# 07-ZYNQ_BANK_502.net
KiCad netlist of a schematic drawn in Altium Designer
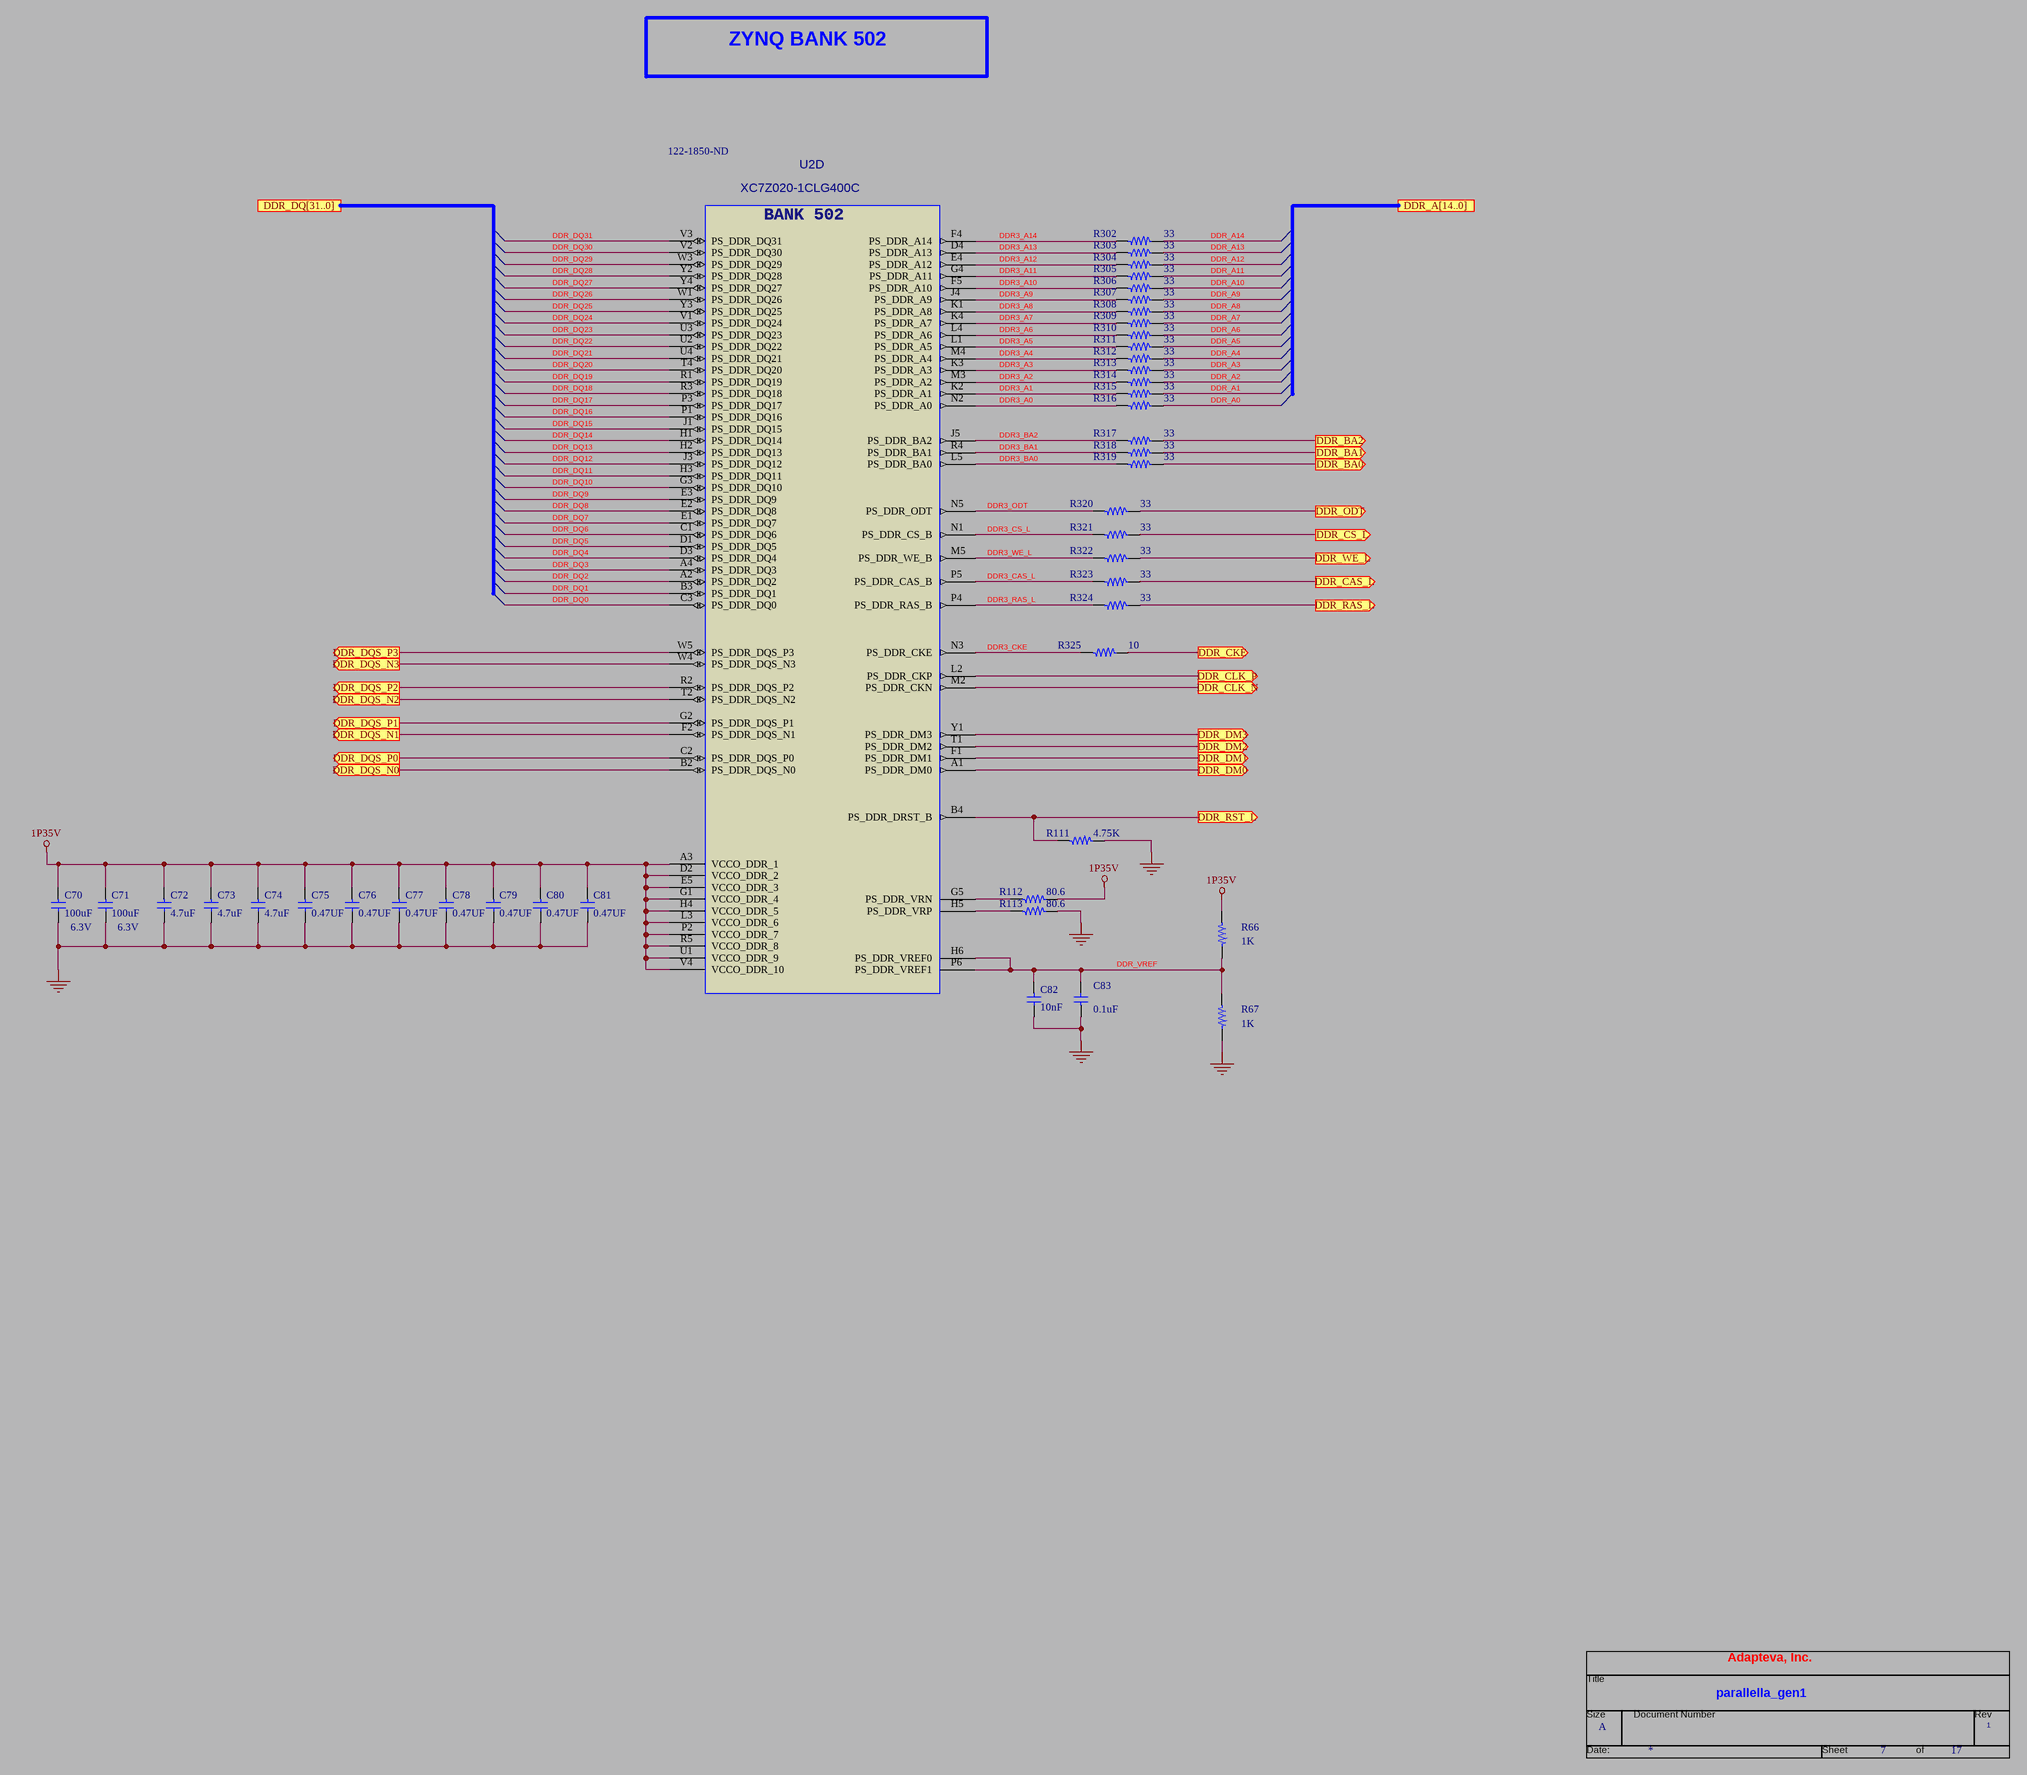
[diagram p0: 07-ZYNQ BANK 502.SchDoc]

(export (version "E")
  (design (tool "Eeschema 10.0.6"))
  (components
    (comp (ref "C70")
      (value "100uF")
      (footprint "C1210")
      (description "CAP, 1210, 100UF, X5R, 6.3V, LOW ESR")
      (fields
        (field (name "VOLTAGE") "6.3V")
        (field (name "MFG PART NO") "GRM32ER60J107ME20L")
        (field (name "MFG") "MURATA")
      )
      (libsource (lib "*") (part "CAP1210_100UF_X5R_LOESR"))
    )
    (comp (ref "C71")
      (value "100uF")
      (footprint "C1210")
      (description "CAP, 1210, 100UF, X5R, 6.3V, LOW ESR")
      (fields
        (field (name "VOLTAGE") "6.3V")
        (field (name "MFG PART NO") "GRM32ER60J107ME20L")
        (field (name "MFG") "MURATA")
      )
      (libsource (lib "*") (part "CAP1210_100UF_X5R_LOESR"))
    )
    (comp (ref "C72")
      (value "4.7uF")
      (footprint "C0402")
      (description "CAP, 0402, 4.7UF, X5R, 6.3V")
      (fields (field (name "MFG PART NO") "C1005X5R0J475K") (field (name "MFG") "TDK"))
      (libsource (lib "*") (part "CAP0402_4P7UF_X5R"))
    )
    (comp (ref "C73")
      (value "4.7uF")
      (footprint "C0402")
      (description "CAP, 0402, 4.7UF, X5R, 6.3V")
      (fields (field (name "MFG PART NO") "C1005X5R0J475K") (field (name "MFG") "TDK"))
      (libsource (lib "*") (part "CAP0402_4P7UF_X5R"))
    )
    (comp (ref "C74")
      (value "4.7uF")
      (footprint "C0402")
      (description "CAP, 0402, 4.7UF, X5R, 6.3V")
      (fields (field (name "MFG PART NO") "C1005X5R0J475K") (field (name "MFG") "TDK"))
      (libsource (lib "*") (part "CAP0402_4P7UF_X5R"))
    )
    (comp (ref "C75")
      (value "0.47UF")
      (footprint "C0402")
      (description "CAP, 0402, 0.47UF, X5R, 16V")
      (fields (field (name "MFG") "TDK") (field (name "MFG PART NO") "C1005X5R1C474K"))
      (libsource (lib "*") (part "CAP0402_0P47UF_X5R"))
    )
    (comp (ref "C76")
      (value "0.47UF")
      (footprint "C0402")
      (description "CAP, 0402, 0.47UF, X5R, 16V")
      (fields (field (name "MFG") "TDK") (field (name "MFG PART NO") "C1005X5R1C474K"))
      (libsource (lib "*") (part "CAP0402_0P47UF_X5R"))
    )
    (comp (ref "C77")
      (value "0.47UF")
      (footprint "C0402")
      (description "CAP, 0402, 0.47UF, X5R, 16V")
      (fields (field (name "MFG") "TDK") (field (name "MFG PART NO") "C1005X5R1C474K"))
      (libsource (lib "*") (part "CAP0402_0P47UF_X5R"))
    )
    (comp (ref "C78")
      (value "0.47UF")
      (footprint "C0402")
      (description "CAP, 0402, 0.47UF, X5R, 16V")
      (fields (field (name "MFG") "TDK") (field (name "MFG PART NO") "C1005X5R1C474K"))
      (libsource (lib "*") (part "CAP0402_0P47UF_X5R"))
    )
    (comp (ref "C79")
      (value "0.47UF")
      (footprint "C0402")
      (description "CAP, 0402, 0.47UF, X5R, 16V")
      (fields (field (name "MFG") "TDK") (field (name "MFG PART NO") "C1005X5R1C474K"))
      (libsource (lib "*") (part "CAP0402_0P47UF_X5R"))
    )
    (comp (ref "C80")
      (value "0.47UF")
      (footprint "C0402")
      (description "CAP, 0402, 0.47UF, X5R, 16V")
      (fields (field (name "MFG") "TDK") (field (name "MFG PART NO") "C1005X5R1C474K"))
      (libsource (lib "*") (part "CAP0402_0P47UF_X5R"))
    )
    (comp (ref "C81")
      (value "0.47UF")
      (footprint "C0402")
      (description "CAP, 0402, 0.47UF, X5R, 16V")
      (fields (field (name "MFG") "TDK") (field (name "MFG PART NO") "C1005X5R1C474K"))
      (libsource (lib "*") (part "CAP0402_0P47UF_X5R"))
    )
    (comp (ref "C82")
      (value "10nF")
      (footprint "C0402")
      (description "CAP, 0402, 10NF, X7R, 16V")
      (fields (field (name "MFG") "TDK") (field (name "MFG PART NO") "C1005X7R1C103K"))
      (libsource (lib "*") (part "CAP0402_10NF_X7R_16V"))
    )
    (comp (ref "C83")
      (value "0.1uF")
      (footprint "C0402")
      (description "CAP, 0402, 0.1UF, X5R, 35V")
      (fields (field (name "MFG PART NO") "GMK105BJ104KV-F") (field (name "MFG") "TAIYO YUDEN"))
      (libsource (lib "*") (part "CAP0402_0P1UF_X5R_35V"))
    )
    (comp (ref "R66")
      (value "1K")
      (footprint "R0402")
      (description "RES, 0402, 1K")
      (fields (field (name "MFG") "VISHAY") (field (name "MFG PART NO") "CRCW04021K00FKED"))
      (libsource (lib "*") (part "RES0402_1K"))
    )
    (comp (ref "R67")
      (value "1K")
      (footprint "R0402")
      (description "RES, 0402, 1K")
      (fields (field (name "MFG") "VISHAY") (field (name "MFG PART NO") "CRCW04021K00FKED"))
      (libsource (lib "*") (part "RES0402_1K"))
    )
    (comp (ref "R111")
      (value "4.75K")
      (footprint "R0402")
      (description "RES, 0402, 4.75K, 1%")
      (fields (field (name "MFG") "VISHAY") (field (name "MFG PART NO") "CRCW04024K75FKED"))
      (libsource (lib "*") (part "RES0402_4K75"))
    )
    (comp (ref "R112")
      (value "80.6")
      (footprint "R0402")
      (description "RES, 0402, 80.6, 1%")
      (fields (field (name "MFG") "VISHAY") (field (name "MFG PART NO") "CRCW040280R6FKED"))
      (libsource (lib "*") (part "RES0402_80P6"))
    )
    (comp (ref "R113")
      (value "80.6")
      (footprint "R0402")
      (description "RES, 0402, 80.6, 1%")
      (fields (field (name "MFG") "VISHAY") (field (name "MFG PART NO") "CRCW040280R6FKED"))
      (libsource (lib "*") (part "RES0402_80P6"))
    )
    (comp (ref "R302")
      (value "33")
      (footprint "R0402")
      (description "RES, 0402, 33, 1%")
      (fields (field (name "MFG") "VISHAY") (field (name "MFG PART NO") "CRCW040233R0FKED"))
      (libsource (lib "*") (part "RES0402_33"))
    )
    (comp (ref "R303")
      (value "33")
      (footprint "R0402")
      (description "RES, 0402, 33, 1%")
      (fields (field (name "MFG") "VISHAY") (field (name "MFG PART NO") "CRCW040233R0FKED"))
      (libsource (lib "*") (part "RES0402_33"))
    )
    (comp (ref "R304")
      (value "33")
      (footprint "R0402")
      (description "RES, 0402, 33, 1%")
      (fields (field (name "MFG") "VISHAY") (field (name "MFG PART NO") "CRCW040233R0FKED"))
      (libsource (lib "*") (part "RES0402_33"))
    )
    (comp (ref "R305")
      (value "33")
      (footprint "R0402")
      (description "RES, 0402, 33, 1%")
      (fields (field (name "MFG") "VISHAY") (field (name "MFG PART NO") "CRCW040233R0FKED"))
      (libsource (lib "*") (part "RES0402_33"))
    )
    (comp (ref "R306")
      (value "33")
      (footprint "R0402")
      (description "RES, 0402, 33, 1%")
      (fields (field (name "MFG") "VISHAY") (field (name "MFG PART NO") "CRCW040233R0FKED"))
      (libsource (lib "*") (part "RES0402_33"))
    )
    (comp (ref "R307")
      (value "33")
      (footprint "R0402")
      (description "RES, 0402, 33, 1%")
      (fields (field (name "MFG") "VISHAY") (field (name "MFG PART NO") "CRCW040233R0FKED"))
      (libsource (lib "*") (part "RES0402_33"))
    )
    (comp (ref "R308")
      (value "33")
      (footprint "R0402")
      (description "RES, 0402, 33, 1%")
      (fields (field (name "MFG") "VISHAY") (field (name "MFG PART NO") "CRCW040233R0FKED"))
      (libsource (lib "*") (part "RES0402_33"))
    )
    (comp (ref "R309")
      (value "33")
      (footprint "R0402")
      (description "RES, 0402, 33, 1%")
      (fields (field (name "MFG") "VISHAY") (field (name "MFG PART NO") "CRCW040233R0FKED"))
      (libsource (lib "*") (part "RES0402_33"))
    )
    (comp (ref "R310")
      (value "33")
      (footprint "R0402")
      (description "RES, 0402, 33, 1%")
      (fields (field (name "MFG") "VISHAY") (field (name "MFG PART NO") "CRCW040233R0FKED"))
      (libsource (lib "*") (part "RES0402_33"))
    )
    (comp (ref "R311")
      (value "33")
      (footprint "R0402")
      (description "RES, 0402, 33, 1%")
      (fields (field (name "MFG") "VISHAY") (field (name "MFG PART NO") "CRCW040233R0FKED"))
      (libsource (lib "*") (part "RES0402_33"))
    )
    (comp (ref "R312")
      (value "33")
      (footprint "R0402")
      (description "RES, 0402, 33, 1%")
      (fields (field (name "MFG") "VISHAY") (field (name "MFG PART NO") "CRCW040233R0FKED"))
      (libsource (lib "*") (part "RES0402_33"))
    )
    (comp (ref "R313")
      (value "33")
      (footprint "R0402")
      (description "RES, 0402, 33, 1%")
      (fields (field (name "MFG") "VISHAY") (field (name "MFG PART NO") "CRCW040233R0FKED"))
      (libsource (lib "*") (part "RES0402_33"))
    )
    (comp (ref "R314")
      (value "33")
      (footprint "R0402")
      (description "RES, 0402, 33, 1%")
      (fields (field (name "MFG") "VISHAY") (field (name "MFG PART NO") "CRCW040233R0FKED"))
      (libsource (lib "*") (part "RES0402_33"))
    )
    (comp (ref "R315")
      (value "33")
      (footprint "R0402")
      (description "RES, 0402, 33, 1%")
      (fields (field (name "MFG") "VISHAY") (field (name "MFG PART NO") "CRCW040233R0FKED"))
      (libsource (lib "*") (part "RES0402_33"))
    )
    (comp (ref "R316")
      (value "33")
      (footprint "R0402")
      (description "RES, 0402, 33, 1%")
      (fields (field (name "MFG") "VISHAY") (field (name "MFG PART NO") "CRCW040233R0FKED"))
      (libsource (lib "*") (part "RES0402_33"))
    )
    (comp (ref "R317")
      (value "33")
      (footprint "R0402")
      (description "RES, 0402, 33, 1%")
      (fields (field (name "MFG") "VISHAY") (field (name "MFG PART NO") "CRCW040233R0FKED"))
      (libsource (lib "*") (part "RES0402_33"))
    )
    (comp (ref "R318")
      (value "33")
      (footprint "R0402")
      (description "RES, 0402, 33, 1%")
      (fields (field (name "MFG") "VISHAY") (field (name "MFG PART NO") "CRCW040233R0FKED"))
      (libsource (lib "*") (part "RES0402_33"))
    )
    (comp (ref "R319")
      (value "33")
      (footprint "R0402")
      (description "RES, 0402, 33, 1%")
      (fields (field (name "MFG") "VISHAY") (field (name "MFG PART NO") "CRCW040233R0FKED"))
      (libsource (lib "*") (part "RES0402_33"))
    )
    (comp (ref "R320")
      (value "33")
      (footprint "R0402")
      (description "RES, 0402, 33, 1%")
      (fields (field (name "MFG") "VISHAY") (field (name "MFG PART NO") "CRCW040233R0FKED"))
      (libsource (lib "*") (part "RES0402_33"))
    )
    (comp (ref "R321")
      (value "33")
      (footprint "R0402")
      (description "RES, 0402, 33, 1%")
      (fields (field (name "MFG") "VISHAY") (field (name "MFG PART NO") "CRCW040233R0FKED"))
      (libsource (lib "*") (part "RES0402_33"))
    )
    (comp (ref "R322")
      (value "33")
      (footprint "R0402")
      (description "RES, 0402, 33, 1%")
      (fields (field (name "MFG") "VISHAY") (field (name "MFG PART NO") "CRCW040233R0FKED"))
      (libsource (lib "*") (part "RES0402_33"))
    )
    (comp (ref "R323")
      (value "33")
      (footprint "R0402")
      (description "RES, 0402, 33, 1%")
      (fields (field (name "MFG") "VISHAY") (field (name "MFG PART NO") "CRCW040233R0FKED"))
      (libsource (lib "*") (part "RES0402_33"))
    )
    (comp (ref "R324")
      (value "33")
      (footprint "R0402")
      (description "RES, 0402, 33, 1%")
      (fields (field (name "MFG") "VISHAY") (field (name "MFG PART NO") "CRCW040233R0FKED"))
      (libsource (lib "*") (part "RES0402_33"))
    )
    (comp (ref "R325")
      (value "10")
      (footprint "R0402")
      (description "RES, 0402, 10, 1%")
      (fields (field (name "MFG PART NO") "CRCW040210R0FKED") (field (name "MFG") "VISHAY"))
      (libsource (lib "*") (part "RES0402_10"))
    )
    (comp (ref "U2")
      (value "7Z020-CLG400")
      (footprint "CBGA400_17SQ_1P6H_P8MMP")
      (description "IC, EPP, XILINX, ZYNQ, 7Z020, CLG400")
      (fields
        (field (name "VENDOR PN") "XC7Z020-1CLG400C")
        (field (name "SUPPLIER PART NUMBER 1") "122-1850-ND")
      )
      (libsource (lib "*") (part "ZYNQ_7Z020_CLG400"))
    )
  )
  (nets
    (net (code "1") (name "/DDR3_A0") (class "Default")
      (node (ref "R316") (pin "1") (pinfunction "1_1") (pintype "passive"))
      (node (ref "U2") (pin "N2") (pinfunction "PS_DDR_A0_N2") (pintype "output"))
    )
    (net (code "2") (name "/DDR3_A1") (class "Default")
      (node (ref "R315") (pin "1") (pinfunction "1_1") (pintype "passive"))
      (node (ref "U2") (pin "K2") (pinfunction "PS_DDR_A1_K2") (pintype "output"))
    )
    (net (code "3") (name "/DDR3_A2") (class "Default")
      (node (ref "R314") (pin "1") (pinfunction "1_1") (pintype "passive"))
      (node (ref "U2") (pin "M3") (pinfunction "PS_DDR_A2_M3") (pintype "output"))
    )
    (net (code "4") (name "/DDR3_A3") (class "Default")
      (node (ref "R313") (pin "1") (pinfunction "1_1") (pintype "passive"))
      (node (ref "U2") (pin "K3") (pinfunction "PS_DDR_A3_K3") (pintype "output"))
    )
    (net (code "5") (name "/DDR3_A4") (class "Default")
      (node (ref "R312") (pin "1") (pinfunction "1_1") (pintype "passive"))
      (node (ref "U2") (pin "M4") (pinfunction "PS_DDR_A4_M4") (pintype "output"))
    )
    (net (code "6") (name "/DDR3_A5") (class "Default")
      (node (ref "R311") (pin "1") (pinfunction "1_1") (pintype "passive"))
      (node (ref "U2") (pin "L1") (pinfunction "PS_DDR_A5_L1") (pintype "output"))
    )
    (net (code "7") (name "/DDR3_A6") (class "Default")
      (node (ref "R310") (pin "1") (pinfunction "1_1") (pintype "passive"))
      (node (ref "U2") (pin "L4") (pinfunction "PS_DDR_A6_L4") (pintype "output"))
    )
    (net (code "8") (name "/DDR3_A7") (class "Default")
      (node (ref "R309") (pin "1") (pinfunction "1_1") (pintype "passive"))
      (node (ref "U2") (pin "K4") (pinfunction "PS_DDR_A7_K4") (pintype "output"))
    )
    (net (code "9") (name "/DDR3_A8") (class "Default")
      (node (ref "R308") (pin "1") (pinfunction "1_1") (pintype "passive"))
      (node (ref "U2") (pin "K1") (pinfunction "PS_DDR_A8_K1") (pintype "output"))
    )
    (net (code "10") (name "/DDR3_A9") (class "Default")
      (node (ref "R307") (pin "1") (pinfunction "1_1") (pintype "passive"))
      (node (ref "U2") (pin "J4") (pinfunction "PS_DDR_A9_J4") (pintype "output"))
    )
    (net (code "11") (name "/DDR3_A10") (class "Default")
      (node (ref "R306") (pin "1") (pinfunction "1_1") (pintype "passive"))
      (node (ref "U2") (pin "F5") (pinfunction "PS_DDR_A10_F5") (pintype "output"))
    )
    (net (code "12") (name "/DDR3_A11") (class "Default")
      (node (ref "R305") (pin "1") (pinfunction "1_1") (pintype "passive"))
      (node (ref "U2") (pin "G4") (pinfunction "PS_DDR_A11_G4") (pintype "output"))
    )
    (net (code "13") (name "/DDR3_A12") (class "Default")
      (node (ref "R304") (pin "1") (pinfunction "1_1") (pintype "passive"))
      (node (ref "U2") (pin "E4") (pinfunction "PS_DDR_A12_E4") (pintype "output"))
    )
    (net (code "14") (name "/DDR3_A13") (class "Default")
      (node (ref "R303") (pin "1") (pinfunction "1_1") (pintype "passive"))
      (node (ref "U2") (pin "D4") (pinfunction "PS_DDR_A13_D4") (pintype "output"))
    )
    (net (code "15") (name "/DDR3_A14") (class "Default")
      (node (ref "R302") (pin "1") (pinfunction "1_1") (pintype "passive"))
      (node (ref "U2") (pin "F4") (pinfunction "PS_DDR_A14_F4") (pintype "output"))
    )
    (net (code "16") (name "/DDR3_BA0") (class "Default")
      (node (ref "R319") (pin "1") (pinfunction "1_1") (pintype "passive"))
      (node (ref "U2") (pin "L5") (pinfunction "PS_DDR_BA0_L5") (pintype "output"))
    )
    (net (code "17") (name "/DDR3_BA1") (class "Default")
      (node (ref "R318") (pin "1") (pinfunction "1_1") (pintype "passive"))
      (node (ref "U2") (pin "R4") (pinfunction "PS_DDR_BA1_R4") (pintype "output"))
    )
    (net (code "18") (name "/DDR3_BA2") (class "Default")
      (node (ref "R317") (pin "1") (pinfunction "1_1") (pintype "passive"))
      (node (ref "U2") (pin "J5") (pinfunction "PS_DDR_BA2_J5") (pintype "output"))
    )
    (net (code "19") (name "/DDR3_CAS_L") (class "Default")
      (node (ref "R323") (pin "1") (pinfunction "1_1") (pintype "passive"))
      (node (ref "U2") (pin "P5") (pinfunction "PS_DDR_CAS_B_P5") (pintype "output"))
    )
    (net (code "20") (name "/DDR3_CKE") (class "Default")
      (node (ref "R325") (pin "1") (pinfunction "1_1") (pintype "passive"))
      (node (ref "U2") (pin "N3") (pinfunction "PS_DDR_CKE_N3") (pintype "output"))
    )
    (net (code "21") (name "/DDR3_CS_L") (class "Default")
      (node (ref "R321") (pin "1") (pinfunction "1_1") (pintype "passive"))
      (node (ref "U2") (pin "N1") (pinfunction "PS_DDR_CS_B_N1") (pintype "output"))
    )
    (net (code "22") (name "/DDR3_ODT") (class "Default")
      (node (ref "R320") (pin "1") (pinfunction "1_1") (pintype "passive"))
      (node (ref "U2") (pin "N5") (pinfunction "PS_DDR_ODT_N5") (pintype "output"))
    )
    (net (code "23") (name "/DDR3_RAS_L") (class "Default")
      (node (ref "R324") (pin "1") (pinfunction "1_1") (pintype "passive"))
      (node (ref "U2") (pin "P4") (pinfunction "PS_DDR_RAS_B_P4") (pintype "output"))
    )
    (net (code "24") (name "/DDR3_WE_L") (class "Default")
      (node (ref "R322") (pin "1") (pinfunction "1_1") (pintype "passive"))
      (node (ref "U2") (pin "M5") (pinfunction "PS_DDR_WE_B_M5") (pintype "output"))
    )
    (net (code "25") (name "/DDR_A0") (class "Default")
      (node (ref "R316") (pin "2") (pinfunction "2_2") (pintype "passive"))
    )
    (net (code "26") (name "/DDR_A1") (class "Default")
      (node (ref "R315") (pin "2") (pinfunction "2_2") (pintype "passive"))
    )
    (net (code "27") (name "/DDR_A2") (class "Default")
      (node (ref "R314") (pin "2") (pinfunction "2_2") (pintype "passive"))
    )
    (net (code "28") (name "/DDR_A3") (class "Default")
      (node (ref "R313") (pin "2") (pinfunction "2_2") (pintype "passive"))
    )
    (net (code "29") (name "/DDR_A4") (class "Default")
      (node (ref "R312") (pin "2") (pinfunction "2_2") (pintype "passive"))
    )
    (net (code "30") (name "/DDR_A5") (class "Default")
      (node (ref "R311") (pin "2") (pinfunction "2_2") (pintype "passive"))
    )
    (net (code "31") (name "/DDR_A6") (class "Default")
      (node (ref "R310") (pin "2") (pinfunction "2_2") (pintype "passive"))
    )
    (net (code "32") (name "/DDR_A7") (class "Default")
      (node (ref "R309") (pin "2") (pinfunction "2_2") (pintype "passive"))
    )
    (net (code "33") (name "/DDR_A8") (class "Default")
      (node (ref "R308") (pin "2") (pinfunction "2_2") (pintype "passive"))
    )
    (net (code "34") (name "/DDR_A9") (class "Default")
      (node (ref "R307") (pin "2") (pinfunction "2_2") (pintype "passive"))
    )
    (net (code "35") (name "/DDR_A10") (class "Default")
      (node (ref "R306") (pin "2") (pinfunction "2_2") (pintype "passive"))
    )
    (net (code "36") (name "/DDR_A11") (class "Default")
      (node (ref "R305") (pin "2") (pinfunction "2_2") (pintype "passive"))
    )
    (net (code "37") (name "/DDR_A12") (class "Default")
      (node (ref "R304") (pin "2") (pinfunction "2_2") (pintype "passive"))
    )
    (net (code "38") (name "/DDR_A13") (class "Default")
      (node (ref "R303") (pin "2") (pinfunction "2_2") (pintype "passive"))
    )
    (net (code "39") (name "/DDR_A14") (class "Default")
      (node (ref "R302") (pin "2") (pinfunction "2_2") (pintype "passive"))
    )
    (net (code "41") (name "/DDR_BA0") (class "Default")
      (node (ref "R319") (pin "2") (pinfunction "2_2") (pintype "passive"))
    )
    (net (code "42") (name "/DDR_BA1") (class "Default")
      (node (ref "R318") (pin "2") (pinfunction "2_2") (pintype "passive"))
    )
    (net (code "43") (name "/DDR_BA2") (class "Default")
      (node (ref "R317") (pin "2") (pinfunction "2_2") (pintype "passive"))
    )
    (net (code "44") (name "/DDR_CAS_L") (class "Default")
      (node (ref "R323") (pin "2") (pinfunction "2_2") (pintype "passive"))
    )
    (net (code "45") (name "/DDR_CKE") (class "Default")
      (node (ref "R325") (pin "2") (pinfunction "2_2") (pintype "passive"))
    )
    (net (code "46") (name "/DDR_CLK_N") (class "Default")
      (node (ref "U2") (pin "M2") (pinfunction "PS_DDR_CKN_M2") (pintype "output"))
    )
    (net (code "47") (name "/DDR_CLK_P") (class "Default")
      (node (ref "U2") (pin "L2") (pinfunction "PS_DDR_CKP_L2") (pintype "output"))
    )
    (net (code "48") (name "/DDR_CS_L") (class "Default")
      (node (ref "R321") (pin "2") (pinfunction "2_2") (pintype "passive"))
    )
    (net (code "49") (name "/DDR_DM0") (class "Default")
      (node (ref "U2") (pin "A1") (pinfunction "PS_DDR_DM0_A1") (pintype "output"))
    )
    (net (code "50") (name "/DDR_DM1") (class "Default")
      (node (ref "U2") (pin "F1") (pinfunction "PS_DDR_DM1_F1") (pintype "output"))
    )
    (net (code "51") (name "/DDR_DM2") (class "Default")
      (node (ref "U2") (pin "T1") (pinfunction "PS_DDR_DM2_T1") (pintype "output"))
    )
    (net (code "52") (name "/DDR_DM3") (class "Default")
      (node (ref "U2") (pin "Y1") (pinfunction "PS_DDR_DM3_Y1") (pintype "output"))
    )
    (net (code "53") (name "/DDR_DQ0") (class "Default")
      (node (ref "U2") (pin "C3") (pinfunction "PS_DDR_DQ0_C3") (pintype "bidirectional"))
    )
    (net (code "54") (name "/DDR_DQ1") (class "Default")
      (node (ref "U2") (pin "B3") (pinfunction "PS_DDR_DQ1_B3") (pintype "bidirectional"))
    )
    (net (code "55") (name "/DDR_DQ2") (class "Default")
      (node (ref "U2") (pin "A2") (pinfunction "PS_DDR_DQ2_A2") (pintype "bidirectional"))
    )
    (net (code "56") (name "/DDR_DQ3") (class "Default")
      (node (ref "U2") (pin "A4") (pinfunction "PS_DDR_DQ3_A4") (pintype "bidirectional"))
    )
    (net (code "57") (name "/DDR_DQ4") (class "Default")
      (node (ref "U2") (pin "D3") (pinfunction "PS_DDR_DQ4_D3") (pintype "bidirectional"))
    )
    (net (code "58") (name "/DDR_DQ5") (class "Default")
      (node (ref "U2") (pin "D1") (pinfunction "PS_DDR_DQ5_D1") (pintype "bidirectional"))
    )
    (net (code "59") (name "/DDR_DQ6") (class "Default")
      (node (ref "U2") (pin "C1") (pinfunction "PS_DDR_DQ6_C1") (pintype "bidirectional"))
    )
    (net (code "60") (name "/DDR_DQ7") (class "Default")
      (node (ref "U2") (pin "E1") (pinfunction "PS_DDR_DQ7_E1") (pintype "bidirectional"))
    )
    (net (code "61") (name "/DDR_DQ8") (class "Default")
      (node (ref "U2") (pin "E2") (pinfunction "PS_DDR_DQ8_E2") (pintype "bidirectional"))
    )
    (net (code "62") (name "/DDR_DQ9") (class "Default")
      (node (ref "U2") (pin "E3") (pinfunction "PS_DDR_DQ9_E3") (pintype "bidirectional"))
    )
    (net (code "63") (name "/DDR_DQ10") (class "Default")
      (node (ref "U2") (pin "G3") (pinfunction "PS_DDR_DQ10_G3") (pintype "bidirectional"))
    )
    (net (code "64") (name "/DDR_DQ11") (class "Default")
      (node (ref "U2") (pin "H3") (pinfunction "PS_DDR_DQ11_H3") (pintype "bidirectional"))
    )
    (net (code "65") (name "/DDR_DQ12") (class "Default")
      (node (ref "U2") (pin "J3") (pinfunction "PS_DDR_DQ12_J3") (pintype "bidirectional"))
    )
    (net (code "66") (name "/DDR_DQ13") (class "Default")
      (node (ref "U2") (pin "H2") (pinfunction "PS_DDR_DQ13_H2") (pintype "bidirectional"))
    )
    (net (code "67") (name "/DDR_DQ14") (class "Default")
      (node (ref "U2") (pin "H1") (pinfunction "PS_DDR_DQ14_H1") (pintype "bidirectional"))
    )
    (net (code "68") (name "/DDR_DQ15") (class "Default")
      (node (ref "U2") (pin "J1") (pinfunction "PS_DDR_DQ15_J1") (pintype "bidirectional"))
    )
    (net (code "69") (name "/DDR_DQ16") (class "Default")
      (node (ref "U2") (pin "P1") (pinfunction "PS_DDR_DQ16_P1") (pintype "bidirectional"))
    )
    (net (code "70") (name "/DDR_DQ17") (class "Default")
      (node (ref "U2") (pin "P3") (pinfunction "PS_DDR_DQ17_P3") (pintype "bidirectional"))
    )
    (net (code "71") (name "/DDR_DQ18") (class "Default")
      (node (ref "U2") (pin "R3") (pinfunction "PS_DDR_DQ18_R3") (pintype "bidirectional"))
    )
    (net (code "72") (name "/DDR_DQ19") (class "Default")
      (node (ref "U2") (pin "R1") (pinfunction "PS_DDR_DQ19_R1") (pintype "bidirectional"))
    )
    (net (code "73") (name "/DDR_DQ20") (class "Default")
      (node (ref "U2") (pin "T4") (pinfunction "PS_DDR_DQ20_T4") (pintype "bidirectional"))
    )
    (net (code "74") (name "/DDR_DQ21") (class "Default")
      (node (ref "U2") (pin "U4") (pinfunction "PS_DDR_DQ21_U4") (pintype "bidirectional"))
    )
    (net (code "75") (name "/DDR_DQ22") (class "Default")
      (node (ref "U2") (pin "U2") (pinfunction "PS_DDR_DQ22_U2") (pintype "bidirectional"))
    )
    (net (code "76") (name "/DDR_DQ23") (class "Default")
      (node (ref "U2") (pin "U3") (pinfunction "PS_DDR_DQ23_U3") (pintype "bidirectional"))
    )
    (net (code "77") (name "/DDR_DQ24") (class "Default")
      (node (ref "U2") (pin "V1") (pinfunction "PS_DDR_DQ24_V1") (pintype "bidirectional"))
    )
    (net (code "78") (name "/DDR_DQ25") (class "Default")
      (node (ref "U2") (pin "Y3") (pinfunction "PS_DDR_DQ25_Y3") (pintype "bidirectional"))
    )
    (net (code "79") (name "/DDR_DQ26") (class "Default")
      (node (ref "U2") (pin "W1") (pinfunction "PS_DDR_DQ26_W1") (pintype "bidirectional"))
    )
    (net (code "80") (name "/DDR_DQ27") (class "Default")
      (node (ref "U2") (pin "Y4") (pinfunction "PS_DDR_DQ27_Y4") (pintype "bidirectional"))
    )
    (net (code "81") (name "/DDR_DQ28") (class "Default")
      (node (ref "U2") (pin "Y2") (pinfunction "PS_DDR_DQ28_Y2") (pintype "bidirectional"))
    )
    (net (code "82") (name "/DDR_DQ29") (class "Default")
      (node (ref "U2") (pin "W3") (pinfunction "PS_DDR_DQ29_W3") (pintype "bidirectional"))
    )
    (net (code "83") (name "/DDR_DQ30") (class "Default")
      (node (ref "U2") (pin "V2") (pinfunction "PS_DDR_DQ30_V2") (pintype "bidirectional"))
    )
    (net (code "84") (name "/DDR_DQ31") (class "Default")
      (node (ref "U2") (pin "V3") (pinfunction "PS_DDR_DQ31_V3") (pintype "bidirectional"))
    )
    (net (code "85") (name "/DDR_DQS_N0") (class "Default")
      (node (ref "U2") (pin "B2") (pinfunction "PS_DDR_DQS_N0_B2") (pintype "bidirectional"))
    )
    (net (code "86") (name "/DDR_DQS_N1") (class "Default")
      (node (ref "U2") (pin "F2") (pinfunction "PS_DDR_DQS_N1_F2") (pintype "bidirectional"))
    )
    (net (code "87") (name "/DDR_DQS_N2") (class "Default")
      (node (ref "U2") (pin "T2") (pinfunction "PS_DDR_DQS_N2_T2") (pintype "bidirectional"))
    )
    (net (code "88") (name "/DDR_DQS_N3") (class "Default")
      (node (ref "U2") (pin "W4") (pinfunction "PS_DDR_DQS_N3_W4") (pintype "bidirectional"))
    )
    (net (code "89") (name "/DDR_DQS_P0") (class "Default")
      (node (ref "U2") (pin "C2") (pinfunction "PS_DDR_DQS_P0_C2") (pintype "bidirectional"))
    )
    (net (code "90") (name "/DDR_DQS_P1") (class "Default")
      (node (ref "U2") (pin "G2") (pinfunction "PS_DDR_DQS_P1_G2") (pintype "bidirectional"))
    )
    (net (code "91") (name "/DDR_DQS_P2") (class "Default")
      (node (ref "U2") (pin "R2") (pinfunction "PS_DDR_DQS_P2_R2") (pintype "bidirectional"))
    )
    (net (code "92") (name "/DDR_DQS_P3") (class "Default")
      (node (ref "U2") (pin "W5") (pinfunction "PS_DDR_DQS_P3_W5") (pintype "bidirectional"))
    )
    (net (code "94") (name "/DDR_ODT") (class "Default")
      (node (ref "R320") (pin "2") (pinfunction "2_2") (pintype "passive"))
    )
    (net (code "95") (name "/DDR_RAS_L") (class "Default")
      (node (ref "R324") (pin "2") (pinfunction "2_2") (pintype "passive"))
    )
    (net (code "96") (name "/DDR_RST_L") (class "Default")
      (node (ref "R111") (pin "1") (pinfunction "1_1") (pintype "passive"))
      (node (ref "U2") (pin "B4") (pinfunction "PS_DDR_DRST_B_B4") (pintype "output"))
    )
    (net (code "97") (name "/DDR_VREF") (class "Default")
      (node (ref "C82") (pin "1") (pinfunction "1_1") (pintype "passive"))
      (node (ref "C83") (pin "2") (pinfunction "2_2") (pintype "passive"))
      (node (ref "R66") (pin "2") (pinfunction "2_2") (pintype "passive"))
      (node (ref "R67") (pin "1") (pinfunction "1_1") (pintype "passive"))
      (node (ref "U2") (pin "H6") (pinfunction "PS_DDR_VREF0_H6") (pintype "power_in"))
      (node (ref "U2") (pin "P6") (pinfunction "PS_DDR_VREF1_P6") (pintype "power_in"))
    )
    (net (code "98") (name "/DDR_WE_L") (class "Default")
      (node (ref "R322") (pin "2") (pinfunction "2_2") (pintype "passive"))
    )
    (net (code "99") (name "1P35V") (class "Default")
      (node (ref "C70") (pin "1") (pinfunction "1_1") (pintype "passive"))
      (node (ref "C71") (pin "1") (pinfunction "1_1") (pintype "passive"))
      (node (ref "C72") (pin "1") (pinfunction "1_1") (pintype "passive"))
      (node (ref "C73") (pin "1") (pinfunction "1_1") (pintype "passive"))
      (node (ref "C74") (pin "1") (pinfunction "1_1") (pintype "passive"))
      (node (ref "C75") (pin "1") (pinfunction "1_1") (pintype "passive"))
      (node (ref "C76") (pin "1") (pinfunction "1_1") (pintype "passive"))
      (node (ref "C77") (pin "1") (pinfunction "1_1") (pintype "passive"))
      (node (ref "C78") (pin "1") (pinfunction "1_1") (pintype "passive"))
      (node (ref "C79") (pin "1") (pinfunction "1_1") (pintype "passive"))
      (node (ref "C80") (pin "1") (pinfunction "1_1") (pintype "passive"))
      (node (ref "C81") (pin "1") (pinfunction "1_1") (pintype "passive"))
      (node (ref "R112") (pin "2") (pinfunction "2_2") (pintype "passive"))
      (node (ref "R66") (pin "1") (pinfunction "1_1") (pintype "passive"))
      (node (ref "U2") (pin "A3") (pinfunction "VCCO_DDR_1_A3") (pintype "power_in"))
      (node (ref "U2") (pin "D2") (pinfunction "VCCO_DDR_2_D2") (pintype "power_in"))
      (node (ref "U2") (pin "E5") (pinfunction "VCCO_DDR_3_E5") (pintype "power_in"))
      (node (ref "U2") (pin "G1") (pinfunction "VCCO_DDR_4_G1") (pintype "power_in"))
      (node (ref "U2") (pin "H4") (pinfunction "VCCO_DDR_5_H4") (pintype "power_in"))
      (node (ref "U2") (pin "L3") (pinfunction "VCCO_DDR_6_L3") (pintype "power_in"))
      (node (ref "U2") (pin "P2") (pinfunction "VCCO_DDR_7_P2") (pintype "power_in"))
      (node (ref "U2") (pin "R5") (pinfunction "VCCO_DDR_8_R5") (pintype "power_in"))
      (node (ref "U2") (pin "U1") (pinfunction "VCCO_DDR_9_U1") (pintype "power_in"))
      (node (ref "U2") (pin "V4") (pinfunction "VCCO_DDR_10_V4") (pintype "power_in"))
    )
    (net (code "100") (name "GND") (class "Default")
      (node (ref "C70") (pin "2") (pinfunction "2_2") (pintype "passive"))
      (node (ref "C71") (pin "2") (pinfunction "2_2") (pintype "passive"))
      (node (ref "C72") (pin "2") (pinfunction "2_2") (pintype "passive"))
      (node (ref "C73") (pin "2") (pinfunction "2_2") (pintype "passive"))
      (node (ref "C74") (pin "2") (pinfunction "2_2") (pintype "passive"))
      (node (ref "C75") (pin "2") (pinfunction "2_2") (pintype "passive"))
      (node (ref "C76") (pin "2") (pinfunction "2_2") (pintype "passive"))
      (node (ref "C77") (pin "2") (pinfunction "2_2") (pintype "passive"))
      (node (ref "C78") (pin "2") (pinfunction "2_2") (pintype "passive"))
      (node (ref "C79") (pin "2") (pinfunction "2_2") (pintype "passive"))
      (node (ref "C80") (pin "2") (pinfunction "2_2") (pintype "passive"))
      (node (ref "C81") (pin "2") (pinfunction "2_2") (pintype "passive"))
      (node (ref "C82") (pin "2") (pinfunction "2_2") (pintype "passive"))
      (node (ref "C83") (pin "1") (pinfunction "1_1") (pintype "passive"))
      (node (ref "R111") (pin "2") (pinfunction "2_2") (pintype "passive"))
      (node (ref "R113") (pin "2") (pinfunction "2_2") (pintype "passive"))
      (node (ref "R67") (pin "2") (pinfunction "2_2") (pintype "passive"))
    )
    (net (code "101") (name "Net-(U2D-PS_DDR_VRN)") (class "Default")
      (node (ref "R112") (pin "1") (pinfunction "1_1") (pintype "passive"))
      (node (ref "U2") (pin "G5") (pinfunction "PS_DDR_VRN_G5") (pintype "power_in"))
    )
    (net (code "102") (name "Net-(U2D-PS_DDR_VRP)") (class "Default")
      (node (ref "R113") (pin "1") (pinfunction "1_1") (pintype "passive"))
      (node (ref "U2") (pin "H5") (pinfunction "PS_DDR_VRP_H5") (pintype "power_in"))
    )
  )
)
